# easySens-RS485-RND_455-00307-V001.net
KiCad netlist of a schematic drawn in EAGLE
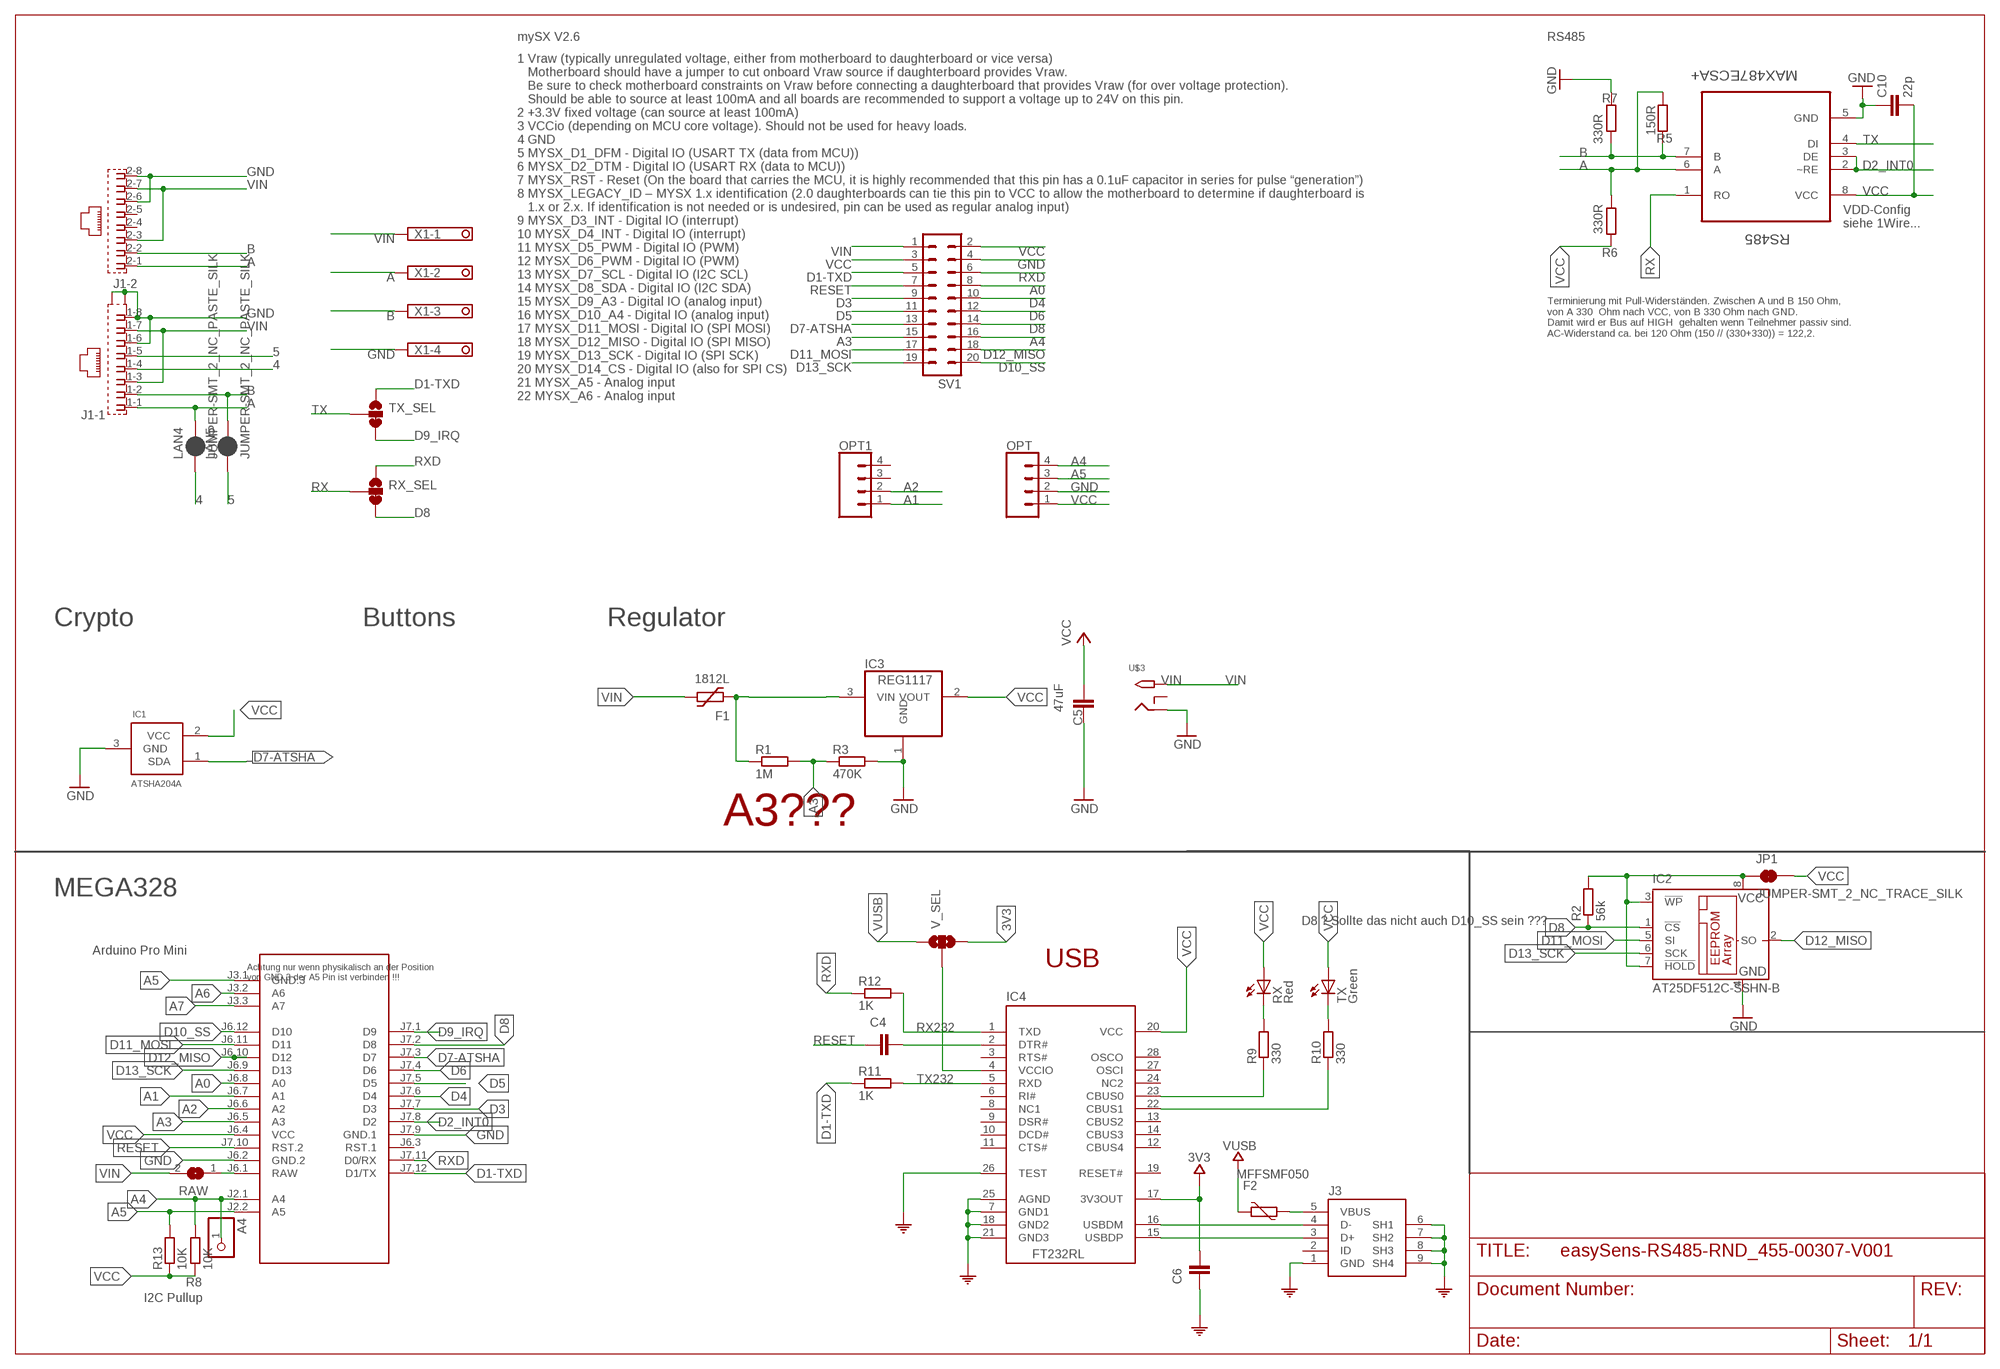
[diagram p0: schematic, sheet 1]

(export (version "E")
  (design (tool "Eeschema 10.0.6"))
  (components
    (comp (ref "A4")
      (value "PINHD-1X1")
      (footprint "eagle-import:1X01")
      (libsource (lib "eagle-import") (part "PINHD-1X1"))
    )
    (comp (ref "C4")
      (value "100nF")
      (footprint "eagle-import:C0805")
      (libsource (lib "eagle-import") (part "resistor@1_C-EUC0805"))
    )
    (comp (ref "C5")
      (value "47uF")
      (footprint "eagle-import:C1210")
      (libsource (lib "eagle-import") (part "C-EUC1210"))
    )
    (comp (ref "C6")
      (value "100nF")
      (footprint "eagle-import:C0805")
      (libsource (lib "eagle-import") (part "resistor@1_C-EUC0805"))
    )
    (comp (ref "C10")
      (value "22p")
      (footprint "eagle-import:C0805")
      (libsource (lib "eagle-import") (part "C-EUC0805"))
    )
    (comp (ref "F1")
      (value "1812L")
      (footprint "eagle-import:1812L")
      (libsource (lib "eagle-import") (part "1812L"))
    )
    (comp (ref "F2")
      (value "MFFSMF050")
      (footprint "eagle-import:0603-1608X90N")
      (fields (field (name "MANUFACTURER") "Bourns Inc "))
      (libsource (lib "eagle-import") (part "PTC"))
    )
    (comp (ref "IC1")
      (value "ATSHA204A")
      (footprint "eagle-import:SOT23")
      (libsource (lib "eagle-import") (part "ATSHA204A"))
    )
    (comp (ref "IC2")
      (value "AT25DF512C-SSHN-B")
      (footprint "eagle-import:SO-08")
      (fields (field (name "MF") "MICROCHIP") (field (name "MPN") "25AA080/SN"))
      (libsource (lib "eagle-import") (part "25SNAA080"))
    )
    (comp (ref "IC3")
      (value "REG1117")
      (footprint "eagle-import:SOT223")
      (libsource (lib "eagle-import") (part "REG1117"))
    )
    (comp (ref "IC4")
      (value "FT232RL")
      (footprint "eagle-import:SSOP28")
      (libsource (lib "eagle-import") (part "0226_FT232RL"))
    )
    (comp (ref "J1")
      (value "RJ45_2X_NARROW_SHILDPINS")
      (footprint "eagle-import:RJ45_2X_NARROW_SHILDPINS")
      (libsource (lib "eagle-import") (part "RJ45_2X_NARROW_SHILDPINS"))
    )
    (comp (ref "J3")
      (value "0219_14850")
      (footprint "eagle-import:USB-MINI-B_2")
      (fields (field (name "PART_NUMBER") "14850"))
      (libsource (lib "eagle-import") (part "0219_14850"))
    )
    (comp (ref "JP1")
      (value "JUMPER-SMT_2_NC_TRACE_SILK")
      (footprint "eagle-import:SMT-JUMPER_2_NC_TRACE_SILK")
      (libsource (lib "eagle-import") (part "JUMPER-SMT_2_NC_TRACE_SILK"))
    )
    (comp (ref "LAN4")
      (value "JUMPER-SMT_2_NC_PASTE_SILK")
      (footprint "eagle-import:SMT-JUMPER_2_NC_PASTE_SILK")
      (libsource (lib "eagle-import") (part "JUMPER-SMT_2_NC_PASTE_SILK"))
    )
    (comp (ref "LAN5")
      (value "JUMPER-SMT_2_NC_PASTE_SILK")
      (footprint "eagle-import:SMT-JUMPER_2_NC_PASTE_SILK")
      (libsource (lib "eagle-import") (part "JUMPER-SMT_2_NC_PASTE_SILK"))
    )
    (comp (ref "M1")
      (value "ARDUINO-PRO-MINI-3.3V#NP")
      (footprint "eagle-import:ARDUINO-PRO-MINI#NP")
      (libsource (lib "eagle-import") (part "ARDUINO-PRO-MINI-#NP3.3V"))
    )
    (comp (ref "OPT")
      (value "CONN_04")
      (footprint "eagle-import:1X04")
      (libsource (lib "eagle-import") (part "CONN_04"))
    )
    (comp (ref "OPT1")
      (value "CONN_04")
      (footprint "eagle-import:1X04")
      (libsource (lib "eagle-import") (part "CONN_04"))
    )
    (comp (ref "R1")
      (value "1M")
      (footprint "eagle-import:M0805")
      (libsource (lib "eagle-import") (part "R-EU_M0805"))
    )
    (comp (ref "R2")
      (value "56k")
      (footprint "eagle-import:M0805")
      (libsource (lib "eagle-import") (part "resistor_R-EU_M0805"))
    )
    (comp (ref "R3")
      (value "470K")
      (footprint "eagle-import:R0805")
      (libsource (lib "eagle-import") (part "R-EU_R0805"))
    )
    (comp (ref "R5")
      (value "150R")
      (footprint "eagle-import:R0805")
      (libsource (lib "eagle-import") (part "R-EU_R0805"))
    )
    (comp (ref "R6")
      (value "330R")
      (footprint "eagle-import:R0805")
      (libsource (lib "eagle-import") (part "R-EU_R0805"))
    )
    (comp (ref "R7")
      (value "330R")
      (footprint "eagle-import:R0805")
      (libsource (lib "eagle-import") (part "R-EU_R0805"))
    )
    (comp (ref "R8")
      (value "10K")
      (footprint "eagle-import:R0805")
      (libsource (lib "eagle-import") (part "R-EU_R0805"))
    )
    (comp (ref "R9")
      (value "330")
      (footprint "eagle-import:R0805")
      (libsource (lib "eagle-import") (part "resistor@1_R-EU_R0805"))
    )
    (comp (ref "R10")
      (value "330")
      (footprint "eagle-import:R0805")
      (libsource (lib "eagle-import") (part "resistor@1_R-EU_R0805"))
    )
    (comp (ref "R11")
      (value "1K")
      (footprint "eagle-import:R0805")
      (libsource (lib "eagle-import") (part "resistor@1_R-EU_R0805"))
    )
    (comp (ref "R12")
      (value "1K")
      (footprint "eagle-import:R0805")
      (libsource (lib "eagle-import") (part "resistor@1_R-EU_R0805"))
    )
    (comp (ref "R13")
      (value "10K")
      (footprint "eagle-import:R0805")
      (libsource (lib "eagle-import") (part "R-EU_R0805"))
    )
    (comp (ref "RAW") (value "SJ") (footprint "eagle-import:SJ") (libsource (lib "eagle-import") (part "SJ")))
    (comp (ref "RS485")
      (value "MAX487ECSA+")
      (footprint "eagle-import:SOIC127P600X175-8N")
      (libsource (lib "eagle-import") (part "MAX487ECSA+"))
    )
    (comp (ref "RX")
      (value "Red")
      (footprint "eagle-import:CHIPLED_0805")
      (fields (field (name "PART_NUMBER") "KTP-2012SURCK"))
      (libsource (lib "eagle-import") (part "0181_KTP-2012SURCK"))
    )
    (comp (ref "RX_SEL")
      (value "JUMPER-SMT_3_1-NC_TRACE_SILK")
      (footprint "eagle-import:SMT-JUMPER_3_1-NC_TRACE_SILK")
      (libsource (lib "eagle-import") (part "JUMPER-SMT_3_1-NC_TRACE_SILK"))
    )
    (comp (ref "SV1")
      (value "MA10-2")
      (footprint "eagle-import:MA10-2")
      (libsource (lib "eagle-import") (part "MA10-2"))
    )
    (comp (ref "TX")
      (value "Green")
      (footprint "eagle-import:CHIPLED_0805")
      (fields (field (name "PART_NUMBER") "KPT-2012SGC"))
      (libsource (lib "eagle-import") (part "0043_KPT-2012SGC"))
    )
    (comp (ref "TX_SEL")
      (value "JUMPER-SMT_3_1-NC_TRACE_SILK")
      (footprint "eagle-import:SMT-JUMPER_3_1-NC_TRACE_SILK")
      (libsource (lib "eagle-import") (part "JUMPER-SMT_3_1-NC_TRACE_SILK"))
    )
    (comp (ref "U$3")
      (value "2.1MMJACKTHM")
      (footprint "eagle-import:PJ-102A")
      (libsource (lib "eagle-import") (part "2.1MMJACKTHM"))
    )
    (comp (ref "V_SEL")
      (value "JUMPER-SMT_3_NO_SILK")
      (footprint "eagle-import:SMT-JUMPER_3_NO_SILK")
      (libsource (lib "eagle-import") (part "JUMPER-SMT_3_NO_SILK"))
    )
    (comp (ref "X1")
      (value "1751264")
      (footprint "eagle-import:1751264")
      (libsource (lib "eagle-import") (part "1751264"))
    )
  )
  (nets
    (net (code "1") (name "/4") (class "Default")
      (node (ref "J1") (pin "1-4") (pinfunction "4_1-4") (pintype "passive"))
      (node (ref "LAN4") (pin "1") (pinfunction "1_1") (pintype "passive"))
    )
    (net (code "2") (name "/5") (class "Default")
      (node (ref "J1") (pin "1-5") (pinfunction "5_1-5") (pintype "passive"))
      (node (ref "LAN5") (pin "1") (pinfunction "1_1") (pintype "passive"))
    )
    (net (code "3") (name "/A") (class "Default")
      (node (ref "J1") (pin "1-1") (pinfunction "1_1-1") (pintype "passive"))
      (node (ref "J1") (pin "2-1") (pinfunction "1_2-1") (pintype "passive"))
      (node (ref "LAN4") (pin "2") (pinfunction "2_2") (pintype "passive"))
      (node (ref "R5") (pin "1") (pinfunction "1_1") (pintype "passive"))
      (node (ref "R6") (pin "2") (pinfunction "2_2") (pintype "passive"))
      (node (ref "RS485") (pin "6") (pinfunction "A_6") (pintype "bidirectional"))
      (node (ref "X1") (pin "2") (pinfunction "K_2") (pintype "passive"))
    )
    (net (code "4") (name "/B") (class "Default")
      (node (ref "J1") (pin "1-2") (pinfunction "2_1-2") (pintype "passive"))
      (node (ref "J1") (pin "2-2") (pinfunction "2_2-2") (pintype "passive"))
      (node (ref "LAN5") (pin "2") (pinfunction "2_2") (pintype "passive"))
      (node (ref "R5") (pin "2") (pinfunction "2_2") (pintype "passive"))
      (node (ref "R7") (pin "1") (pinfunction "1_1") (pintype "passive"))
      (node (ref "RS485") (pin "7") (pinfunction "B_7") (pintype "bidirectional"))
      (node (ref "X1") (pin "3") (pinfunction "K_3") (pintype "passive"))
    )
    (net (code "5") (name "/RX232") (class "Default")
      (node (ref "IC4") (pin "1") (pinfunction "TXD_1") (pintype "output"))
      (node (ref "R12") (pin "2") (pinfunction "2_2") (pintype "passive"))
    )
    (net (code "6") (name "/TX") (class "Default")
      (node (ref "RS485") (pin "4") (pinfunction "DI_4") (pintype "input"))
      (node (ref "TX_SEL") (pin "2") (pinfunction "2_2") (pintype "passive"))
    )
    (net (code "7") (name "/TX232") (class "Default")
      (node (ref "IC4") (pin "5") (pinfunction "RXD_5") (pintype "input"))
      (node (ref "R11") (pin "2") (pinfunction "2_2") (pintype "passive"))
    )
    (net (code "8") (name "3V3") (class "Default")
      (node (ref "C6") (pin "2") (pinfunction "2_2") (pintype "passive"))
      (node (ref "IC4") (pin "17") (pinfunction "3V3OUT_17") (pintype "power_in"))
      (node (ref "V_SEL") (pin "3") (pinfunction "3_3") (pintype "passive"))
    )
    (net (code "9") (name "A0") (class "Default")
      (node (ref "M1") (pin "J6.8") (pinfunction "A0_J6.8") (pintype "bidirectional"))
      (node (ref "SV1") (pin "8") (pinfunction "8_8") (pintype "passive"))
    )
    (net (code "10") (name "A1") (class "Default")
      (node (ref "M1") (pin "J6.7") (pinfunction "A1_J6.7") (pintype "bidirectional"))
      (node (ref "OPT1") (pin "1") (pinfunction "1_1") (pintype "passive"))
    )
    (net (code "11") (name "A2") (class "Default")
      (node (ref "M1") (pin "J6.6") (pinfunction "A2_J6.6") (pintype "bidirectional"))
      (node (ref "OPT1") (pin "2") (pinfunction "2_2") (pintype "passive"))
    )
    (net (code "12") (name "A3") (class "Default")
      (node (ref "M1") (pin "J6.5") (pinfunction "A3_J6.5") (pintype "bidirectional"))
      (node (ref "R1") (pin "2") (pinfunction "2_2") (pintype "passive"))
      (node (ref "R3") (pin "1") (pinfunction "1_1") (pintype "passive"))
      (node (ref "SV1") (pin "15") (pinfunction "15_15") (pintype "passive"))
    )
    (net (code "13") (name "A4") (class "Default")
      (node (ref "A4") (pin "1") (pinfunction "1_1") (pintype "passive"))
      (node (ref "M1") (pin "J2.1") (pinfunction "A4_J2.1") (pintype "bidirectional"))
      (node (ref "OPT") (pin "4") (pinfunction "4_4") (pintype "passive"))
      (node (ref "R8") (pin "2") (pinfunction "2_2") (pintype "passive"))
      (node (ref "SV1") (pin "16") (pinfunction "16_16") (pintype "passive"))
    )
    (net (code "14") (name "A5") (class "Default")
      (node (ref "M1") (pin "J2.2") (pinfunction "A5_J2.2") (pintype "bidirectional"))
      (node (ref "M1") (pin "J3.1") (pinfunction "GND.3_J3.1") (pintype "bidirectional"))
      (node (ref "OPT") (pin "3") (pinfunction "3_3") (pintype "passive"))
      (node (ref "R13") (pin "2") (pinfunction "2_2") (pintype "passive"))
    )
    (net (code "15") (name "A6") (class "Default")
      (node (ref "M1") (pin "J3.2") (pinfunction "A6_J3.2") (pintype "bidirectional"))
    )
    (net (code "16") (name "A7") (class "Default")
      (node (ref "M1") (pin "J3.3") (pinfunction "A7_J3.3") (pintype "bidirectional"))
    )
    (net (code "17") (name "COM") (class "Default")
      (node (ref "C6") (pin "1") (pinfunction "1_1") (pintype "passive"))
      (node (ref "IC4") (pin "18") (pinfunction "GND2_18") (pintype "power_in"))
      (node (ref "IC4") (pin "21") (pinfunction "GND3_21") (pintype "power_in"))
      (node (ref "IC4") (pin "25") (pinfunction "AGND_25") (pintype "power_in"))
      (node (ref "IC4") (pin "26") (pinfunction "TEST_26") (pintype "bidirectional"))
      (node (ref "IC4") (pin "7") (pinfunction "GND1_7") (pintype "power_in"))
      (node (ref "J3") (pin "1") (pinfunction "GND_1") (pintype "passive"))
      (node (ref "J3") (pin "6") (pinfunction "SH1_6") (pintype "passive"))
      (node (ref "J3") (pin "7") (pinfunction "SH2_7") (pintype "passive"))
      (node (ref "J3") (pin "8") (pinfunction "SH3_8") (pintype "passive"))
      (node (ref "J3") (pin "9") (pinfunction "SH4_9") (pintype "passive"))
    )
    (net (code "18") (name "D1-TXD") (class "Default")
      (node (ref "M1") (pin "J7.12") (pinfunction "D1/TX_J7.12") (pintype "bidirectional"))
      (node (ref "R11") (pin "1") (pinfunction "1_1") (pintype "passive"))
      (node (ref "SV1") (pin "5") (pinfunction "5_5") (pintype "passive"))
      (node (ref "TX_SEL") (pin "1") (pinfunction "1_1") (pintype "passive"))
    )
    (net (code "19") (name "D2_INT0") (class "Default")
      (node (ref "M1") (pin "J7.8") (pinfunction "D2_J7.8") (pintype "bidirectional"))
      (node (ref "RS485") (pin "2") (pinfunction "~{RE}_2") (pintype "input"))
      (node (ref "RS485") (pin "3") (pinfunction "DE_3") (pintype "input"))
    )
    (net (code "20") (name "D3") (class "Default")
      (node (ref "M1") (pin "J7.7") (pinfunction "D3_J7.7") (pintype "bidirectional"))
      (node (ref "SV1") (pin "9") (pinfunction "9_9") (pintype "passive"))
    )
    (net (code "21") (name "D4") (class "Default")
      (node (ref "M1") (pin "J7.6") (pinfunction "D4_J7.6") (pintype "bidirectional"))
      (node (ref "SV1") (pin "10") (pinfunction "10_10") (pintype "passive"))
    )
    (net (code "22") (name "D5") (class "Default")
      (node (ref "M1") (pin "J7.5") (pinfunction "D5_J7.5") (pintype "bidirectional"))
      (node (ref "SV1") (pin "11") (pinfunction "11_11") (pintype "passive"))
    )
    (net (code "23") (name "D6") (class "Default")
      (node (ref "M1") (pin "J7.4") (pinfunction "D6_J7.4") (pintype "bidirectional"))
      (node (ref "SV1") (pin "12") (pinfunction "12_12") (pintype "passive"))
    )
    (net (code "24") (name "D7-ATSHA") (class "Default")
      (node (ref "IC1") (pin "1") (pinfunction "SDA_1") (pintype "bidirectional"))
      (node (ref "M1") (pin "J7.3") (pinfunction "D7_J7.3") (pintype "bidirectional"))
      (node (ref "SV1") (pin "13") (pinfunction "13_13") (pintype "passive"))
    )
    (net (code "25") (name "D8") (class "Default")
      (node (ref "IC2") (pin "1") (pinfunction "~{CS}_1") (pintype "input"))
      (node (ref "M1") (pin "J7.2") (pinfunction "D8_J7.2") (pintype "bidirectional"))
      (node (ref "R2") (pin "1") (pinfunction "1_1") (pintype "passive"))
      (node (ref "RX_SEL") (pin "3") (pinfunction "3_3") (pintype "passive"))
      (node (ref "SV1") (pin "14") (pinfunction "14_14") (pintype "passive"))
    )
    (net (code "26") (name "D9_IRQ") (class "Default")
      (node (ref "M1") (pin "J7.1") (pinfunction "D9_J7.1") (pintype "bidirectional"))
      (node (ref "TX_SEL") (pin "3") (pinfunction "3_3") (pintype "passive"))
    )
    (net (code "27") (name "D10_SS") (class "Default")
      (node (ref "M1") (pin "J6.12") (pinfunction "D10_J6.12") (pintype "bidirectional"))
      (node (ref "SV1") (pin "20") (pinfunction "20_20") (pintype "passive"))
    )
    (net (code "28") (name "D11_MOSI") (class "Default")
      (node (ref "IC2") (pin "5") (pinfunction "SI_5") (pintype "input"))
      (node (ref "M1") (pin "J6.11") (pinfunction "D11_J6.11") (pintype "bidirectional"))
      (node (ref "SV1") (pin "17") (pinfunction "17_17") (pintype "passive"))
    )
    (net (code "29") (name "D12_MISO") (class "Default")
      (node (ref "IC2") (pin "2") (pinfunction "SO_2") (pintype "bidirectional"))
      (node (ref "M1") (pin "J6.10") (pinfunction "D12_J6.10") (pintype "bidirectional"))
      (node (ref "SV1") (pin "18") (pinfunction "18_18") (pintype "passive"))
    )
    (net (code "30") (name "D13_SCK") (class "Default")
      (node (ref "IC2") (pin "6") (pinfunction "SCK_6") (pintype "input"))
      (node (ref "M1") (pin "J6.9") (pinfunction "D13_J6.9") (pintype "bidirectional"))
      (node (ref "SV1") (pin "19") (pinfunction "19_19") (pintype "passive"))
    )
    (net (code "31") (name "GND") (class "Default")
      (node (ref "C10") (pin "1") (pinfunction "1_1") (pintype "passive"))
      (node (ref "C5") (pin "1") (pinfunction "1_1") (pintype "passive"))
      (node (ref "IC1") (pin "3") (pinfunction "GND_3") (pintype "bidirectional"))
      (node (ref "IC2") (pin "4") (pinfunction "GND_4") (pintype "power_in"))
      (node (ref "IC3") (pin "1") (pinfunction "GND_1") (pintype "power_in"))
      (node (ref "J1") (pin "1-6") (pinfunction "6_1-6") (pintype "passive"))
      (node (ref "J1") (pin "1-8") (pinfunction "8_1-8") (pintype "passive"))
      (node (ref "J1") (pin "2-6") (pinfunction "6_2-6") (pintype "passive"))
      (node (ref "J1") (pin "2-8") (pinfunction "8_2-8") (pintype "passive"))
      (node (ref "J1") (pin "G1") (pinfunction "S1_G1") (pintype "passive"))
      (node (ref "J1") (pin "G3") (pinfunction "S2_G3") (pintype "passive"))
      (node (ref "M1") (pin "J6.2") (pinfunction "GND.2_J6.2") (pintype "power_in"))
      (node (ref "M1") (pin "J7.9") (pinfunction "GND.1_J7.9") (pintype "power_in"))
      (node (ref "OPT") (pin "2") (pinfunction "2_2") (pintype "passive"))
      (node (ref "R3") (pin "2") (pinfunction "2_2") (pintype "passive"))
      (node (ref "R7") (pin "2") (pinfunction "2_2") (pintype "passive"))
      (node (ref "RS485") (pin "5") (pinfunction "GND_5") (pintype "passive"))
      (node (ref "SV1") (pin "4") (pinfunction "4_4") (pintype "passive"))
      (node (ref "U$3") (pin "RING") (pinfunction "RING_RING") (pintype "bidirectional"))
      (node (ref "X1") (pin "4") (pinfunction "K_4") (pintype "passive"))
    )
    (net (code "32") (name "Net-(F1-1)") (class "Default")
      (node (ref "F1") (pin "P$1") (pinfunction "1_P$1") (pintype "passive"))
      (node (ref "IC3") (pin "3") (pinfunction "VIN_3") (pintype "input"))
      (node (ref "R1") (pin "1") (pinfunction "1_1") (pintype "passive"))
    )
    (net (code "33") (name "Net-(IC2-VCC)") (class "Default")
      (node (ref "IC2") (pin "3") (pinfunction "~{WP}_3") (pintype "input"))
      (node (ref "IC2") (pin "7") (pinfunction "~{HOLD}_7") (pintype "input"))
      (node (ref "IC2") (pin "8") (pinfunction "VCC_8") (pintype "power_in"))
      (node (ref "JP1") (pin "1") (pinfunction "1_1") (pintype "passive"))
      (node (ref "R2") (pin "2") (pinfunction "2_2") (pintype "passive"))
    )
    (net (code "34") (name "Net-(IC4-CBUS0)") (class "Default")
      (node (ref "IC4") (pin "23") (pinfunction "CBUS0_23") (pintype "bidirectional"))
      (node (ref "R9") (pin "1") (pinfunction "1_1") (pintype "passive"))
    )
    (net (code "35") (name "Net-(IC4-CBUS1)") (class "Default")
      (node (ref "IC4") (pin "22") (pinfunction "CBUS1_22") (pintype "bidirectional"))
      (node (ref "R10") (pin "1") (pinfunction "1_1") (pintype "passive"))
    )
    (net (code "36") (name "Net-(IC4-DTR#)") (class "Default")
      (node (ref "C4") (pin "2") (pinfunction "2_2") (pintype "passive"))
      (node (ref "IC4") (pin "2") (pinfunction "DTR#_2") (pintype "output"))
    )
    (net (code "37") (name "Net-(IC4-USBDM)") (class "Default")
      (node (ref "IC4") (pin "16") (pinfunction "USBDM_16") (pintype "bidirectional"))
      (node (ref "J3") (pin "4") (pinfunction "D-_4") (pintype "bidirectional"))
    )
    (net (code "38") (name "Net-(IC4-USBDP)") (class "Default")
      (node (ref "IC4") (pin "15") (pinfunction "USBDP_15") (pintype "bidirectional"))
      (node (ref "J3") (pin "3") (pinfunction "D+_3") (pintype "bidirectional"))
    )
    (net (code "39") (name "Net-(IC4-VCCIO)") (class "Default")
      (node (ref "IC4") (pin "4") (pinfunction "VCCIO_4") (pintype "power_in"))
      (node (ref "V_SEL") (pin "2") (pinfunction "2_2") (pintype "passive"))
    )
    (net (code "40") (name "Net-(J3-VBUS)") (class "Default")
      (node (ref "F2") (pin "2") (pinfunction "2_2") (pintype "passive"))
      (node (ref "J3") (pin "5") (pinfunction "VBUS_5") (pintype "power_in"))
    )
    (net (code "41") (name "Net-(M1-RAW)") (class "Default")
      (node (ref "M1") (pin "J6.1") (pinfunction "RAW_J6.1") (pintype "power_in"))
      (node (ref "RAW") (pin "1") (pinfunction "1_1") (pintype "passive"))
    )
    (net (code "42") (name "Net-(R9-Pad2)") (class "Default")
      (node (ref "R9") (pin "2") (pinfunction "2_2") (pintype "passive"))
      (node (ref "RX") (pin "C") (pinfunction "C_C") (pintype "passive"))
    )
    (net (code "43") (name "Net-(R10-Pad2)") (class "Default")
      (node (ref "R10") (pin "2") (pinfunction "2_2") (pintype "passive"))
      (node (ref "TX") (pin "C") (pinfunction "C_C") (pintype "passive"))
    )
    (net (code "44") (name "RESET") (class "Default")
      (node (ref "C4") (pin "1") (pinfunction "1_1") (pintype "passive"))
      (node (ref "M1") (pin "J7.10") (pinfunction "RST.2_J7.10") (pintype "bidirectional"))
      (node (ref "SV1") (pin "7") (pinfunction "7_7") (pintype "passive"))
    )
    (net (code "45") (name "RX") (class "Default")
      (node (ref "RS485") (pin "1") (pinfunction "RO_1") (pintype "output"))
      (node (ref "RX_SEL") (pin "2") (pinfunction "2_2") (pintype "passive"))
    )
    (net (code "46") (name "RXD") (class "Default")
      (node (ref "M1") (pin "J7.11") (pinfunction "D0/RX_J7.11") (pintype "bidirectional"))
      (node (ref "R12") (pin "1") (pinfunction "1_1") (pintype "passive"))
      (node (ref "RX_SEL") (pin "1") (pinfunction "1_1") (pintype "passive"))
      (node (ref "SV1") (pin "6") (pinfunction "6_6") (pintype "passive"))
    )
    (net (code "47") (name "VCC") (class "Default")
      (node (ref "C10") (pin "2") (pinfunction "2_2") (pintype "passive"))
      (node (ref "C5") (pin "2") (pinfunction "2_2") (pintype "passive"))
      (node (ref "IC1") (pin "2") (pinfunction "VCC_2") (pintype "bidirectional"))
      (node (ref "IC3") (pin "2") (pinfunction "VOUT_2") (pintype "output"))
      (node (ref "IC4") (pin "20") (pinfunction "VCC_20") (pintype "power_in"))
      (node (ref "JP1") (pin "2") (pinfunction "2_2") (pintype "passive"))
      (node (ref "M1") (pin "J6.4") (pinfunction "VCC_J6.4") (pintype "power_in"))
      (node (ref "OPT") (pin "1") (pinfunction "1_1") (pintype "passive"))
      (node (ref "R13") (pin "1") (pinfunction "1_1") (pintype "passive"))
      (node (ref "R6") (pin "1") (pinfunction "1_1") (pintype "passive"))
      (node (ref "R8") (pin "1") (pinfunction "1_1") (pintype "passive"))
      (node (ref "RS485") (pin "8") (pinfunction "VCC_8") (pintype "power_in"))
      (node (ref "RX") (pin "A") (pinfunction "A_A") (pintype "passive"))
      (node (ref "SV1") (pin "2") (pinfunction "2_2") (pintype "passive"))
      (node (ref "SV1") (pin "3") (pinfunction "3_3") (pintype "passive"))
      (node (ref "TX") (pin "A") (pinfunction "A_A") (pintype "passive"))
    )
    (net (code "48") (name "VIN") (class "Default")
      (node (ref "F1") (pin "P$2") (pinfunction "2_P$2") (pintype "passive"))
      (node (ref "J1") (pin "1-3") (pinfunction "3_1-3") (pintype "passive"))
      (node (ref "J1") (pin "1-7") (pinfunction "7_1-7") (pintype "passive"))
      (node (ref "J1") (pin "2-3") (pinfunction "3_2-3") (pintype "passive"))
      (node (ref "J1") (pin "2-7") (pinfunction "7_2-7") (pintype "passive"))
      (node (ref "RAW") (pin "2") (pinfunction "2_2") (pintype "passive"))
      (node (ref "SV1") (pin "1") (pinfunction "1_1") (pintype "passive"))
      (node (ref "U$3") (pin "TIP") (pinfunction "TIP_TIP") (pintype "bidirectional"))
      (node (ref "X1") (pin "1") (pinfunction "K_1") (pintype "passive"))
    )
    (net (code "49") (name "VUSB") (class "Default")
      (node (ref "F2") (pin "1") (pinfunction "1_1") (pintype "passive"))
      (node (ref "V_SEL") (pin "1") (pinfunction "1_1") (pintype "passive"))
    )
    (net (code "50") (name "unconnected-(IC4-CBUS2-Pad13)") (class "Default")
      (node (ref "IC4") (pin "13") (pinfunction "CBUS2_13") (pintype "bidirectional"))
    )
    (net (code "51") (name "unconnected-(IC4-CBUS3-Pad14)") (class "Default")
      (node (ref "IC4") (pin "14") (pinfunction "CBUS3_14") (pintype "bidirectional"))
    )
    (net (code "52") (name "unconnected-(IC4-CBUS4-Pad12)") (class "Default")
      (node (ref "IC4") (pin "12") (pinfunction "CBUS4_12") (pintype "bidirectional"))
    )
    (net (code "53") (name "unconnected-(IC4-CTS#-Pad11)") (class "Default")
      (node (ref "IC4") (pin "11") (pinfunction "CTS#_11") (pintype "bidirectional"))
    )
    (net (code "54") (name "unconnected-(IC4-DCD#-Pad10)") (class "Default")
      (node (ref "IC4") (pin "10") (pinfunction "DCD#_10") (pintype "bidirectional"))
    )
    (net (code "55") (name "unconnected-(IC4-DSR#-Pad9)") (class "Default")
      (node (ref "IC4") (pin "9") (pinfunction "DSR#_9") (pintype "bidirectional"))
    )
    (net (code "56") (name "unconnected-(IC4-NC1-Pad8)") (class "Default")
      (node (ref "IC4") (pin "8") (pinfunction "NC1_8") (pintype "bidirectional"))
    )
    (net (code "57") (name "unconnected-(IC4-NC2-Pad24)") (class "Default")
      (node (ref "IC4") (pin "24") (pinfunction "NC2_24") (pintype "no_connect"))
    )
    (net (code "58") (name "unconnected-(IC4-OSCI-Pad27)") (class "Default")
      (node (ref "IC4") (pin "27") (pinfunction "OSCI_27") (pintype "bidirectional"))
    )
    (net (code "59") (name "unconnected-(IC4-OSCO-Pad28)") (class "Default")
      (node (ref "IC4") (pin "28") (pinfunction "OSCO_28") (pintype "output"))
    )
    (net (code "60") (name "unconnected-(IC4-RESET#-Pad19)") (class "Default")
      (node (ref "IC4") (pin "19") (pinfunction "RESET#_19") (pintype "bidirectional"))
    )
    (net (code "61") (name "unconnected-(IC4-RI#-Pad6)") (class "Default")
      (node (ref "IC4") (pin "6") (pinfunction "RI#_6") (pintype "bidirectional"))
    )
    (net (code "62") (name "unconnected-(IC4-RTS#-Pad3)") (class "Default")
      (node (ref "IC4") (pin "3") (pinfunction "RTS#_3") (pintype "output"))
    )
    (net (code "63") (name "unconnected-(J1B-4-Pad2-4)") (class "Default")
      (node (ref "J1") (pin "2-4") (pinfunction "4_2-4") (pintype "passive"))
    )
    (net (code "64") (name "unconnected-(J1B-5-Pad2-5)") (class "Default")
      (node (ref "J1") (pin "2-5") (pinfunction "5_2-5") (pintype "passive"))
    )
    (net (code "65") (name "unconnected-(J3-ID-Pad2)") (class "Default")
      (node (ref "J3") (pin "2") (pinfunction "ID_2") (pintype "bidirectional"))
    )
    (net (code "66") (name "unconnected-(M1-RST.1-PadJ6.3)") (class "Default")
      (node (ref "M1") (pin "J6.3") (pinfunction "RST.1_J6.3") (pintype "bidirectional"))
    )
    (net (code "67") (name "unconnected-(OPT1-Pad3)") (class "Default")
      (node (ref "OPT1") (pin "3") (pinfunction "3_3") (pintype "passive"))
    )
    (net (code "68") (name "unconnected-(OPT1-Pad4)") (class "Default")
      (node (ref "OPT1") (pin "4") (pinfunction "4_4") (pintype "passive"))
    )
    (net (code "69") (name "unconnected-(U$3-PadRING_SW)") (class "Default")
      (node (ref "U$3") (pin "RING_SW") (pinfunction "RING_SW_RING_SW") (pintype "bidirectional"))
    )
  )
)
